# wizneteval.net
KiCad netlist of a schematic drawn in EAGLE
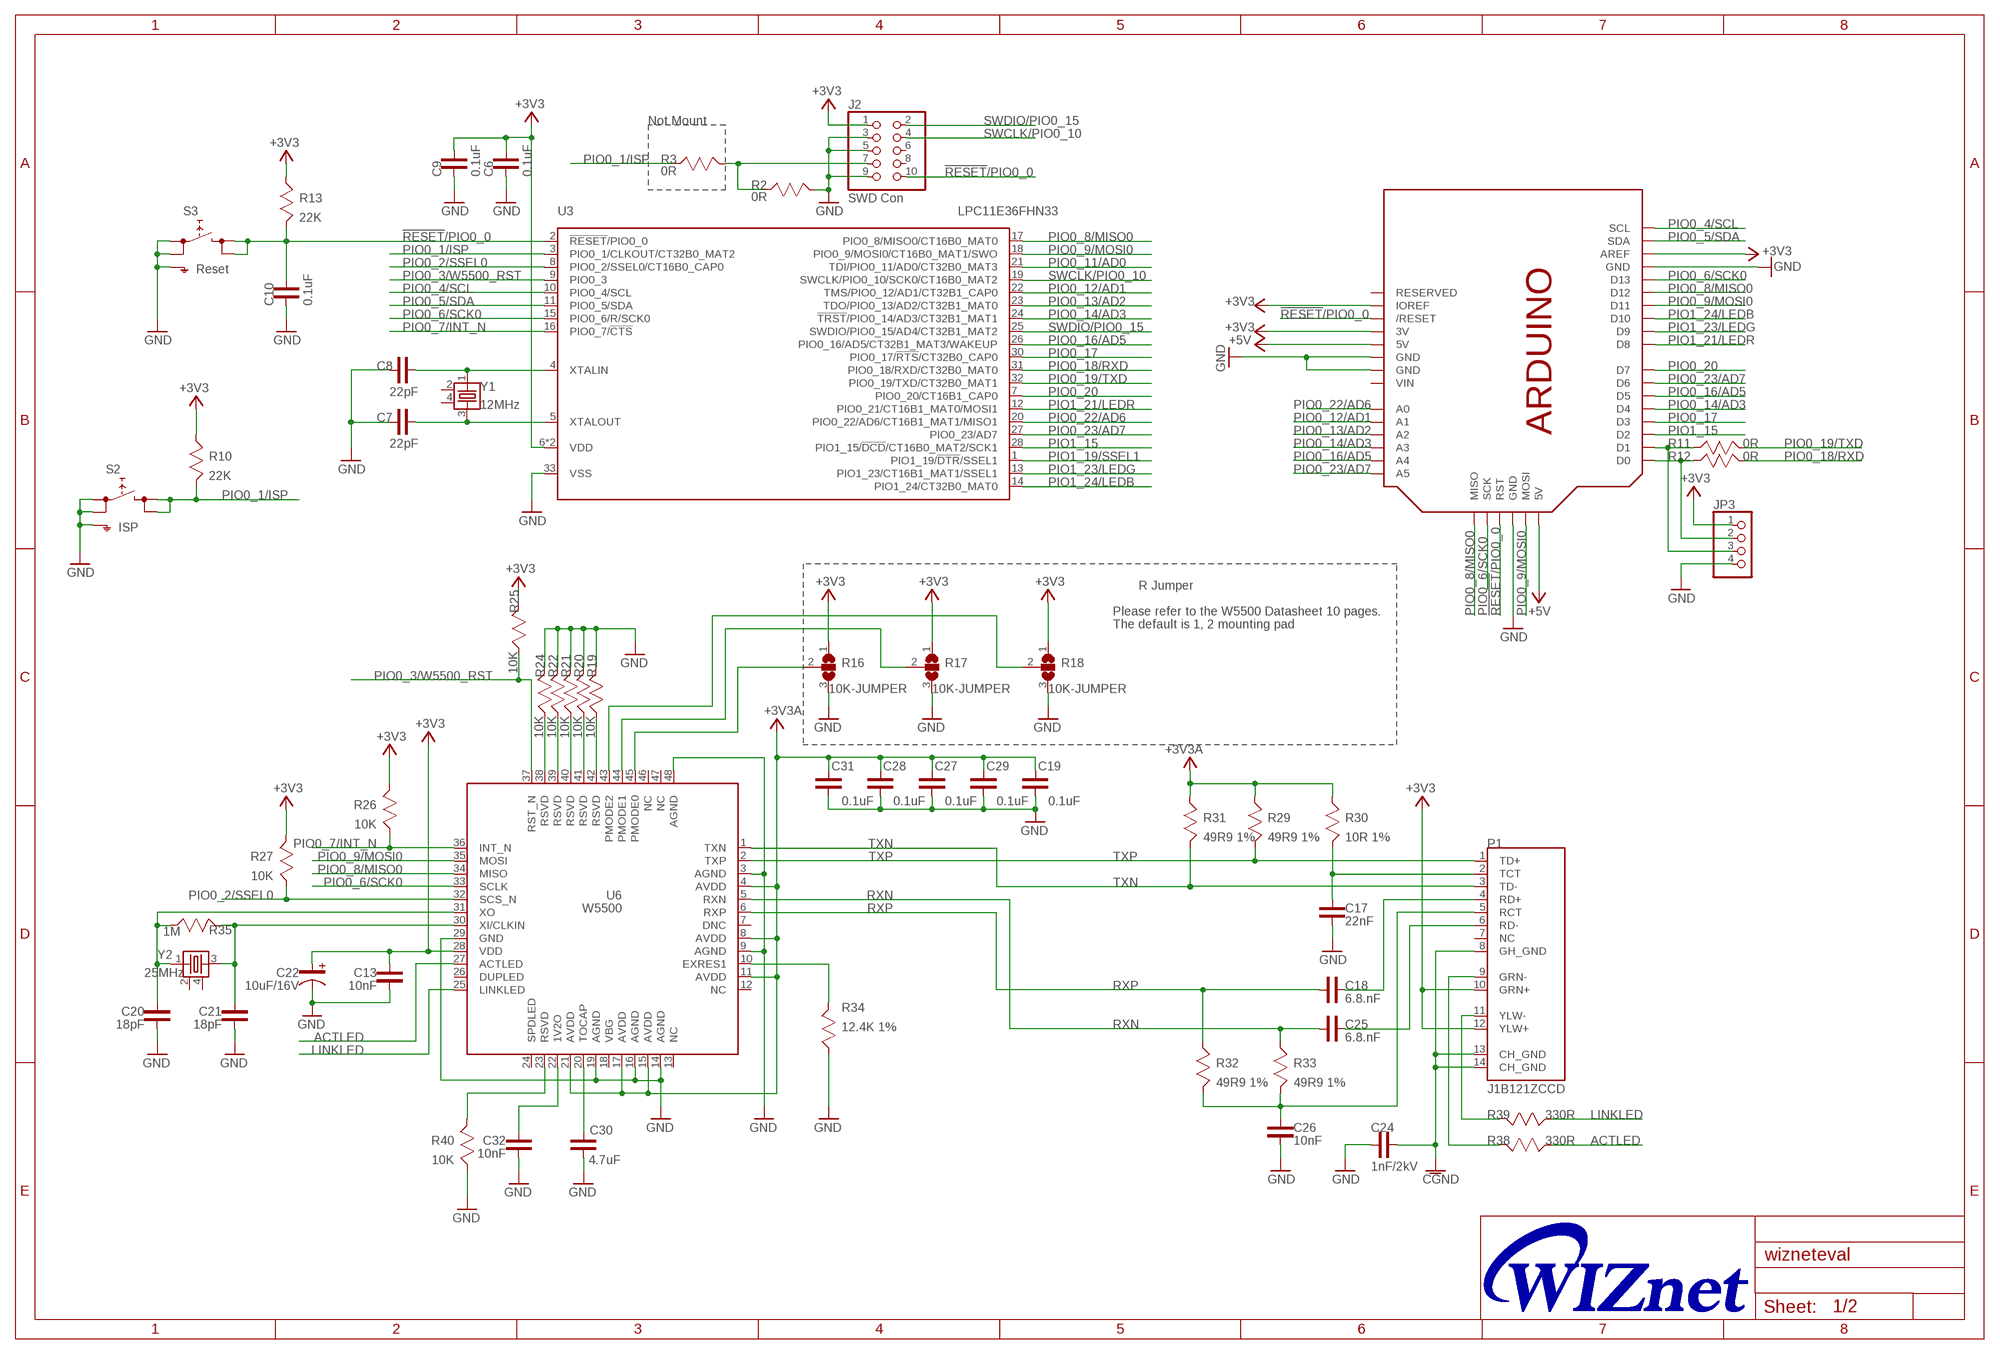
[diagram p0: schematic, sheet 1]
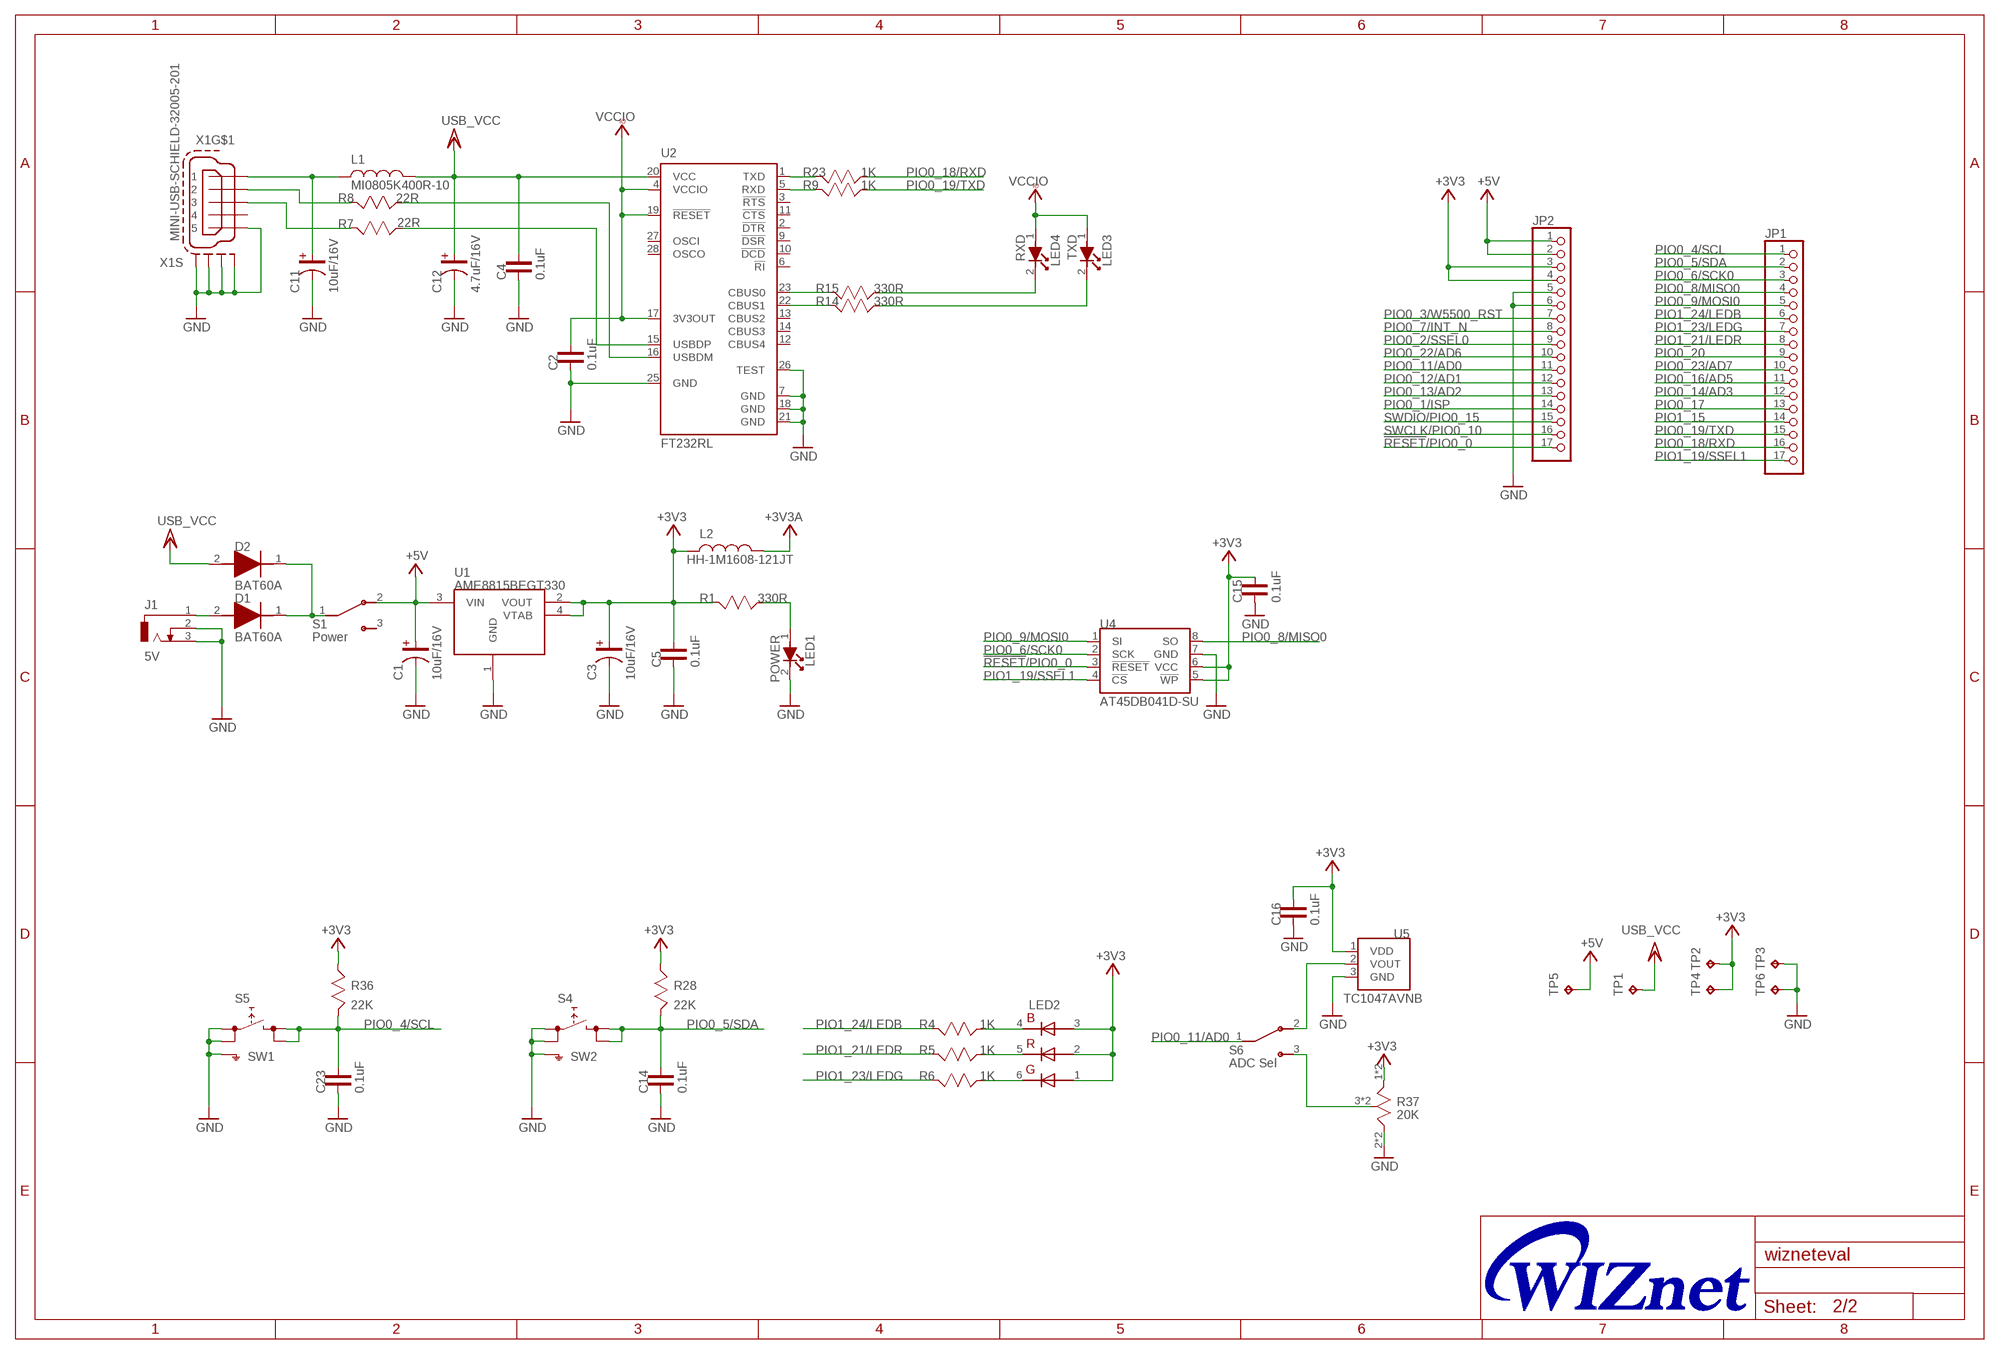
[diagram p1: schematic, sheet 2]

(export (version "E")
  (design (tool "Eeschema 10.0.6"))
  (components
    (comp (ref "$$U$3")
      (value "ARDUINO_R3_ICSP")
      (footprint "eagle-import:ARDUINOR3_ICSP")
      (libsource (lib "eagle-import") (part "ARDUINO_R3_ICSP"))
    )
    (comp (ref "C6")
      (value "0.1uF")
      (footprint "eagle-import:C-1608")
      (libsource (lib "eagle-import") (part "C-1608"))
    )
    (comp (ref "C7")
      (value "22pF")
      (footprint "eagle-import:C-1608")
      (libsource (lib "eagle-import") (part "C-1608"))
    )
    (comp (ref "C8")
      (value "22pF")
      (footprint "eagle-import:C-1608")
      (libsource (lib "eagle-import") (part "C-1608"))
    )
    (comp (ref "C9")
      (value "0.1uF")
      (footprint "eagle-import:C-1608")
      (libsource (lib "eagle-import") (part "C-1608"))
    )
    (comp (ref "C10")
      (value "0.1uF")
      (footprint "eagle-import:C-1608")
      (libsource (lib "eagle-import") (part "C-1608"))
    )
    (comp (ref "C13")
      (value "10nF")
      (footprint "eagle-import:C-1608")
      (libsource (lib "eagle-import") (part "C-1608"))
    )
    (comp (ref "C17")
      (value "22nF")
      (footprint "eagle-import:C-1608")
      (libsource (lib "eagle-import") (part "C-1608"))
    )
    (comp (ref "C18")
      (value "6.8.nF")
      (footprint "eagle-import:C-1608")
      (libsource (lib "eagle-import") (part "C-1608"))
    )
    (comp (ref "C19")
      (value "0.1uF")
      (footprint "eagle-import:C-1608")
      (libsource (lib "eagle-import") (part "C-1608"))
    )
    (comp (ref "C20")
      (value "18pF")
      (footprint "eagle-import:C-1608")
      (libsource (lib "eagle-import") (part "C-1608"))
    )
    (comp (ref "C21")
      (value "18pF")
      (footprint "eagle-import:C-1608")
      (libsource (lib "eagle-import") (part "C-1608"))
    )
    (comp (ref "C22")
      (value "10uF/16V")
      (footprint "eagle-import:C-3216(TANTAL)")
      (libsource (lib "eagle-import") (part "C-3216(TANTAL)"))
    )
    (comp (ref "C24")
      (value "1nF/2kV")
      (footprint "eagle-import:C-4520")
      (libsource (lib "eagle-import") (part "C-4520"))
    )
    (comp (ref "C25")
      (value "6.8.nF")
      (footprint "eagle-import:C-1608")
      (libsource (lib "eagle-import") (part "C-1608"))
    )
    (comp (ref "C26")
      (value "10nF")
      (footprint "eagle-import:C-1608")
      (libsource (lib "eagle-import") (part "C-1608"))
    )
    (comp (ref "C27")
      (value "0.1uF")
      (footprint "eagle-import:C-1608")
      (libsource (lib "eagle-import") (part "C-1608"))
    )
    (comp (ref "C28")
      (value "0.1uF")
      (footprint "eagle-import:C-1608")
      (libsource (lib "eagle-import") (part "C-1608"))
    )
    (comp (ref "C29")
      (value "0.1uF")
      (footprint "eagle-import:C-1608")
      (libsource (lib "eagle-import") (part "C-1608"))
    )
    (comp (ref "C30")
      (value "4.7uF")
      (footprint "eagle-import:C-2012")
      (libsource (lib "eagle-import") (part "C-2012"))
    )
    (comp (ref "C31")
      (value "0.1uF")
      (footprint "eagle-import:C-1608")
      (libsource (lib "eagle-import") (part "C-1608"))
    )
    (comp (ref "C32")
      (value "10nF")
      (footprint "eagle-import:C-1608")
      (libsource (lib "eagle-import") (part "C-1608"))
    )
    (comp (ref "J2")
      (value "SWD Con")
      (footprint "eagle-import:2X5_1.27")
      (libsource (lib "eagle-import") (part "2X5_1.27"))
    )
    (comp (ref "JP3")
      (value "PINHD-1X4")
      (footprint "eagle-import:1X04")
      (libsource (lib "eagle-import") (part "PINHD-1X4"))
    )
    (comp (ref "P1")
      (value "J1B121ZCCD")
      (footprint "eagle-import:J1B121ZCCD")
      (libsource (lib "eagle-import") (part "J1B121ZCCD"))
    )
    (comp (ref "R2")
      (value "0R")
      (footprint "eagle-import:R-1608")
      (libsource (lib "eagle-import") (part "R-1608"))
    )
    (comp (ref "R3")
      (value "0R")
      (footprint "eagle-import:R-1608")
      (libsource (lib "eagle-import") (part "R-1608"))
    )
    (comp (ref "R10")
      (value "22K")
      (footprint "eagle-import:R-1608")
      (libsource (lib "eagle-import") (part "R-1608"))
    )
    (comp (ref "R11")
      (value "0R")
      (footprint "eagle-import:R-1608")
      (libsource (lib "eagle-import") (part "R-1608"))
    )
    (comp (ref "R12")
      (value "0R")
      (footprint "eagle-import:R-1608")
      (libsource (lib "eagle-import") (part "R-1608"))
    )
    (comp (ref "R13")
      (value "22K")
      (footprint "eagle-import:R-1608")
      (libsource (lib "eagle-import") (part "R-1608"))
    )
    (comp (ref "R16")
      (value "10K-JUMPER")
      (footprint "eagle-import:R-1608-JUMPER")
      (libsource (lib "eagle-import") (part "R-1608-JUMPER"))
    )
    (comp (ref "R17")
      (value "10K-JUMPER")
      (footprint "eagle-import:R-1608-JUMPER")
      (libsource (lib "eagle-import") (part "R-1608-JUMPER"))
    )
    (comp (ref "R18")
      (value "10K-JUMPER")
      (footprint "eagle-import:R-1608-JUMPER")
      (libsource (lib "eagle-import") (part "R-1608-JUMPER"))
    )
    (comp (ref "R19")
      (value "10K")
      (footprint "eagle-import:R-1608")
      (libsource (lib "eagle-import") (part "R-1608"))
    )
    (comp (ref "R20")
      (value "10K")
      (footprint "eagle-import:R-1608")
      (libsource (lib "eagle-import") (part "R-1608"))
    )
    (comp (ref "R21")
      (value "10K")
      (footprint "eagle-import:R-1608")
      (libsource (lib "eagle-import") (part "R-1608"))
    )
    (comp (ref "R22")
      (value "10K")
      (footprint "eagle-import:R-1608")
      (libsource (lib "eagle-import") (part "R-1608"))
    )
    (comp (ref "R24")
      (value "10K")
      (footprint "eagle-import:R-1608")
      (libsource (lib "eagle-import") (part "R-1608"))
    )
    (comp (ref "R25")
      (value "10K")
      (footprint "eagle-import:R-1608")
      (libsource (lib "eagle-import") (part "R-1608"))
    )
    (comp (ref "R26")
      (value "10K")
      (footprint "eagle-import:R-1608")
      (libsource (lib "eagle-import") (part "R-1608"))
    )
    (comp (ref "R27")
      (value "10K")
      (footprint "eagle-import:R-1608")
      (libsource (lib "eagle-import") (part "R-1608"))
    )
    (comp (ref "R29")
      (value "49R9 1%")
      (footprint "eagle-import:R-1608")
      (libsource (lib "eagle-import") (part "R-1608"))
    )
    (comp (ref "R30")
      (value "10R 1%")
      (footprint "eagle-import:R-1608")
      (libsource (lib "eagle-import") (part "R-1608"))
    )
    (comp (ref "R31")
      (value "49R9 1%")
      (footprint "eagle-import:R-1608")
      (libsource (lib "eagle-import") (part "R-1608"))
    )
    (comp (ref "R32")
      (value "49R9 1%")
      (footprint "eagle-import:R-1608")
      (libsource (lib "eagle-import") (part "R-1608"))
    )
    (comp (ref "R33")
      (value "49R9 1%")
      (footprint "eagle-import:R-1608")
      (libsource (lib "eagle-import") (part "R-1608"))
    )
    (comp (ref "R34")
      (value "12.4K 1%")
      (footprint "eagle-import:R-1608")
      (libsource (lib "eagle-import") (part "R-1608"))
    )
    (comp (ref "R35")
      (value "1M")
      (footprint "eagle-import:R-1608")
      (libsource (lib "eagle-import") (part "R-1608"))
    )
    (comp (ref "R38")
      (value "330R")
      (footprint "eagle-import:R-1608")
      (libsource (lib "eagle-import") (part "R-1608"))
    )
    (comp (ref "R39")
      (value "330R")
      (footprint "eagle-import:R-1608")
      (libsource (lib "eagle-import") (part "R-1608"))
    )
    (comp (ref "R40")
      (value "10K")
      (footprint "eagle-import:R-1608")
      (libsource (lib "eagle-import") (part "R-1608"))
    )
    (comp (ref "S2")
      (value "ISP")
      (footprint "eagle-import:SKHMPXE010")
      (libsource (lib "eagle-import") (part "SKHMPE010S"))
    )
    (comp (ref "S3")
      (value "Reset")
      (footprint "eagle-import:SKHMPXE010")
      (libsource (lib "eagle-import") (part "SKHMPE010S"))
    )
    (comp (ref "U3")
      (value "LPC11E36FHN33")
      (footprint "eagle-import:SOT-HVQFN33")
      (libsource (lib "eagle-import") (part "LPC11E36FHN33"))
    )
    (comp (ref "U6")
      (value "W5500")
      (footprint "eagle-import:W5500")
      (libsource (lib "eagle-import") (part "W5500"))
    )
    (comp (ref "Y1")
      (value "12MHz")
      (footprint "eagle-import:XTAL3225")
      (libsource (lib "eagle-import") (part "XTAL3225"))
    )
    (comp (ref "Y2")
      (value "25MHz")
      (footprint "eagle-import:XTAL3225")
      (libsource (lib "eagle-import") (part "XTAL3225"))
    )
    (comp (ref "C1")
      (value "10uF/16V")
      (footprint "eagle-import:C-3216(TANTAL)")
      (libsource (lib "eagle-import") (part "C-3216(TANTAL)"))
    )
    (comp (ref "C2")
      (value "0.1uF")
      (footprint "eagle-import:C-1608")
      (libsource (lib "eagle-import") (part "C-1608"))
    )
    (comp (ref "C3")
      (value "10uF/16V")
      (footprint "eagle-import:C-3216(TANTAL)")
      (libsource (lib "eagle-import") (part "C-3216(TANTAL)"))
    )
    (comp (ref "C4")
      (value "0.1uF")
      (footprint "eagle-import:C-1608")
      (libsource (lib "eagle-import") (part "C-1608"))
    )
    (comp (ref "C5")
      (value "0.1uF")
      (footprint "eagle-import:C-1608")
      (libsource (lib "eagle-import") (part "C-1608"))
    )
    (comp (ref "C11")
      (value "10uF/16V")
      (footprint "eagle-import:C-3216(TANTAL)")
      (libsource (lib "eagle-import") (part "C-3216(TANTAL)"))
    )
    (comp (ref "C12")
      (value "4.7uF/16V")
      (footprint "eagle-import:C-3216(TANTAL)")
      (libsource (lib "eagle-import") (part "C-3216(TANTAL)"))
    )
    (comp (ref "C14")
      (value "0.1uF")
      (footprint "eagle-import:C-1608")
      (libsource (lib "eagle-import") (part "C-1608"))
    )
    (comp (ref "C15")
      (value "0.1uF")
      (footprint "eagle-import:C-1608")
      (libsource (lib "eagle-import") (part "C-1608"))
    )
    (comp (ref "C16")
      (value "0.1uF")
      (footprint "eagle-import:C-1608")
      (libsource (lib "eagle-import") (part "C-1608"))
    )
    (comp (ref "C23")
      (value "0.1uF")
      (footprint "eagle-import:C-1608")
      (libsource (lib "eagle-import") (part "C-1608"))
    )
    (comp (ref "D1")
      (value "BAT60A")
      (footprint "eagle-import:BAT60A")
      (libsource (lib "eagle-import") (part "BAT60A"))
    )
    (comp (ref "D2")
      (value "BAT60A")
      (footprint "eagle-import:BAT60A")
      (libsource (lib "eagle-import") (part "BAT60A"))
    )
    (comp (ref "J1")
      (value "5V")
      (footprint "eagle-import:DCJ0202")
      (libsource (lib "eagle-import") (part "DCJ0202"))
    )
    (comp (ref "JP1")
      (value "PINHD-1X17")
      (footprint "eagle-import:1X17")
      (libsource (lib "eagle-import") (part "PINHD-1X17"))
    )
    (comp (ref "JP2")
      (value "PINHD-1X17")
      (footprint "eagle-import:1X17")
      (libsource (lib "eagle-import") (part "PINHD-1X17"))
    )
    (comp (ref "L1")
      (value "MI0805K400R-10")
      (footprint "eagle-import:L-2012")
      (libsource (lib "eagle-import") (part "L-2012"))
    )
    (comp (ref "L2")
      (value "HH-1M1608-121JT")
      (footprint "eagle-import:L-1608")
      (libsource (lib "eagle-import") (part "L-1608"))
    )
    (comp (ref "LED1")
      (value "POWER")
      (footprint "eagle-import:LED-1608")
      (libsource (lib "eagle-import") (part "LED-1608"))
    )
    (comp (ref "LED2")
      (value "LS5050RGB5050")
      (footprint "eagle-import:LS5050RGB")
      (libsource (lib "eagle-import") (part "LS5050RGB5050"))
    )
    (comp (ref "LED3")
      (value "TXD")
      (footprint "eagle-import:LED-1608")
      (libsource (lib "eagle-import") (part "LED-1608"))
    )
    (comp (ref "LED4")
      (value "RXD")
      (footprint "eagle-import:LED-1608")
      (libsource (lib "eagle-import") (part "LED-1608"))
    )
    (comp (ref "R1")
      (value "330R")
      (footprint "eagle-import:R-1608")
      (libsource (lib "eagle-import") (part "R-1608"))
    )
    (comp (ref "R4")
      (value "1K")
      (footprint "eagle-import:R-1608")
      (libsource (lib "eagle-import") (part "R-1608"))
    )
    (comp (ref "R5")
      (value "1K")
      (footprint "eagle-import:R-1608")
      (libsource (lib "eagle-import") (part "R-1608"))
    )
    (comp (ref "R6")
      (value "1K")
      (footprint "eagle-import:R-1608")
      (libsource (lib "eagle-import") (part "R-1608"))
    )
    (comp (ref "R7")
      (value "22R")
      (footprint "eagle-import:R-1608")
      (libsource (lib "eagle-import") (part "R-1608"))
    )
    (comp (ref "R8")
      (value "22R")
      (footprint "eagle-import:R-1608")
      (libsource (lib "eagle-import") (part "R-1608"))
    )
    (comp (ref "R9")
      (value "1K")
      (footprint "eagle-import:R-1608")
      (libsource (lib "eagle-import") (part "R-1608"))
    )
    (comp (ref "R14")
      (value "330R")
      (footprint "eagle-import:R-1608")
      (libsource (lib "eagle-import") (part "R-1608"))
    )
    (comp (ref "R15")
      (value "330R")
      (footprint "eagle-import:R-1608")
      (libsource (lib "eagle-import") (part "R-1608"))
    )
    (comp (ref "R23")
      (value "1K")
      (footprint "eagle-import:R-1608")
      (libsource (lib "eagle-import") (part "R-1608"))
    )
    (comp (ref "R28")
      (value "22K")
      (footprint "eagle-import:R-1608")
      (libsource (lib "eagle-import") (part "R-1608"))
    )
    (comp (ref "R36")
      (value "22K")
      (footprint "eagle-import:R-1608")
      (libsource (lib "eagle-import") (part "R-1608"))
    )
    (comp (ref "R37")
      (value "20K")
      (footprint "eagle-import:RES-VAR-PT10(DUAL)")
      (libsource (lib "eagle-import") (part "RES-VAR-PT10DAUL"))
    )
    (comp (ref "S1")
      (value "Power")
      (footprint "eagle-import:IMMS-12H")
      (libsource (lib "eagle-import") (part "IMMS-12H"))
    )
    (comp (ref "S4")
      (value "SW2")
      (footprint "eagle-import:SKHMPXE010")
      (libsource (lib "eagle-import") (part "SKHMPE010S"))
    )
    (comp (ref "S5")
      (value "SW1")
      (footprint "eagle-import:SKHMPXE010")
      (libsource (lib "eagle-import") (part "SKHMPE010S"))
    )
    (comp (ref "S6")
      (value "ADC Sel")
      (footprint "eagle-import:IMMS-12H")
      (libsource (lib "eagle-import") (part "IMMS-12H"))
    )
    (comp (ref "TP1")
      (value "TPB1,27")
      (footprint "eagle-import:B1,27")
      (libsource (lib "eagle-import") (part "TPB1,27"))
    )
    (comp (ref "TP2")
      (value "TPB1,27")
      (footprint "eagle-import:B1,27")
      (libsource (lib "eagle-import") (part "TPB1,27"))
    )
    (comp (ref "TP3")
      (value "TPB1,27")
      (footprint "eagle-import:B1,27")
      (libsource (lib "eagle-import") (part "TPB1,27"))
    )
    (comp (ref "TP4")
      (value "TPB1,27")
      (footprint "eagle-import:B1,27")
      (libsource (lib "eagle-import") (part "TPB1,27"))
    )
    (comp (ref "TP5")
      (value "TPB1,27")
      (footprint "eagle-import:B1,27")
      (libsource (lib "eagle-import") (part "TPB1,27"))
    )
    (comp (ref "TP6")
      (value "TPB1,27")
      (footprint "eagle-import:B1,27")
      (libsource (lib "eagle-import") (part "TPB1,27"))
    )
    (comp (ref "U1")
      (value "AME8815BEGT330")
      (footprint "eagle-import:SOT-223")
      (libsource (lib "eagle-import") (part "AME8815BEGT330"))
    )
    (comp (ref "U2")
      (value "FT232RL")
      (footprint "eagle-import:SSOP28")
      (libsource (lib "eagle-import") (part "FT232RL"))
    )
    (comp (ref "U4")
      (value "AT45DB041D-SU")
      (footprint "eagle-import:8S2")
      (libsource (lib "eagle-import") (part "AT45DB041D-SU"))
    )
    (comp (ref "U5")
      (value "TC1047AVNB")
      (footprint "eagle-import:SOT23")
      (libsource (lib "eagle-import") (part "TC1047AVNB"))
    )
    (comp (ref "X1")
      (value "MINI-USB-SCHIELD-32005-201")
      (footprint "eagle-import:32005-201")
      (libsource (lib "eagle-import") (part "MINI-USB-SCHIELD-32005-201"))
    )
  )
  (nets
    (net (code "1") (name "+3V3") (class "Default")
      (node (ref "$$U$3") (pin "3V") (pinfunction "3V_3V") (pintype "power_in"))
      (node (ref "$$U$3") (pin "AREF") (pinfunction "AREF_AREF") (pintype "bidirectional"))
      (node (ref "$$U$3") (pin "IOREF") (pinfunction "IOREF_IOREF") (pintype "output"))
      (node (ref "C13") (pin "2") (pinfunction "P$2_2") (pintype "passive"))
      (node (ref "C15") (pin "2") (pinfunction "P$2_2") (pintype "passive"))
      (node (ref "C16") (pin "2") (pinfunction "P$2_2") (pintype "passive"))
      (node (ref "C22") (pin "1") (pinfunction "1_1") (pintype "passive"))
      (node (ref "C3") (pin "1") (pinfunction "1_1") (pintype "passive"))
      (node (ref "C5") (pin "2") (pinfunction "P$2_2") (pintype "passive"))
      (node (ref "C6") (pin "2") (pinfunction "P$2_2") (pintype "passive"))
      (node (ref "C9") (pin "2") (pinfunction "P$2_2") (pintype "passive"))
      (node (ref "J2") (pin "1") (pinfunction "1_1") (pintype "passive"))
      (node (ref "JP2") (pin "3") (pinfunction "3_3") (pintype "passive"))
      (node (ref "JP2") (pin "4") (pinfunction "4_4") (pintype "passive"))
      (node (ref "JP3") (pin "1") (pinfunction "1_1") (pintype "passive"))
      (node (ref "L2") (pin "1") (pinfunction "1_1") (pintype "passive"))
      (node (ref "LED2") (pin "1") (pinfunction "GREEN_A_1") (pintype "bidirectional"))
      (node (ref "LED2") (pin "2") (pinfunction "RED_A_2") (pintype "bidirectional"))
      (node (ref "LED2") (pin "3") (pinfunction "BLUE_A_3") (pintype "bidirectional"))
      (node (ref "P1") (pin "10") (pinfunction "GRN+_10") (pintype "passive"))
      (node (ref "P1") (pin "12") (pinfunction "YLW+_12") (pintype "passive"))
      (node (ref "R1") (pin "1") (pinfunction "P$1_1") (pintype "passive"))
      (node (ref "R10") (pin "2") (pinfunction "P$2_2") (pintype "passive"))
      (node (ref "R13") (pin "2") (pinfunction "P$2_2") (pintype "passive"))
      (node (ref "R16") (pin "1") (pinfunction "1_1") (pintype "passive"))
      (node (ref "R17") (pin "1") (pinfunction "1_1") (pintype "passive"))
      (node (ref "R18") (pin "1") (pinfunction "1_1") (pintype "passive"))
      (node (ref "R25") (pin "2") (pinfunction "P$2_2") (pintype "passive"))
      (node (ref "R26") (pin "2") (pinfunction "P$2_2") (pintype "passive"))
      (node (ref "R27") (pin "2") (pinfunction "P$2_2") (pintype "passive"))
      (node (ref "R28") (pin "2") (pinfunction "P$2_2") (pintype "passive"))
      (node (ref "R36") (pin "2") (pinfunction "P$2_2") (pintype "passive"))
      (node (ref "R37") (pin "1") (pinfunction "P$1_1") (pintype "passive"))
      (node (ref "R37") (pin "P$1") (pinfunction "P$1_P$1") (pintype "passive"))
      (node (ref "TP2") (pin "TP") (pinfunction "TP_TP") (pintype "input"))
      (node (ref "TP4") (pin "TP") (pinfunction "TP_TP") (pintype "input"))
      (node (ref "U1") (pin "2") (pinfunction "VOUT_2") (pintype "passive"))
      (node (ref "U1") (pin "4") (pinfunction "VTAB_4") (pintype "passive"))
      (node (ref "U3") (pin "29") (pinfunction "VDD_29") (pintype "power_in"))
      (node (ref "U3") (pin "6") (pinfunction "VDD_6") (pintype "power_in"))
      (node (ref "U4") (pin "5") (pinfunction "~{WP}_5") (pintype "passive"))
      (node (ref "U4") (pin "6") (pinfunction "VCC_6") (pintype "passive"))
      (node (ref "U5") (pin "1") (pinfunction "VDD_1") (pintype "passive"))
      (node (ref "U6") (pin "28") (pinfunction "VDD_28") (pintype "passive"))
    )
    (net (code "2") (name "+3V3A") (class "Default")
      (node (ref "C19") (pin "2") (pinfunction "P$2_2") (pintype "passive"))
      (node (ref "C27") (pin "2") (pinfunction "P$2_2") (pintype "passive"))
      (node (ref "C28") (pin "2") (pinfunction "P$2_2") (pintype "passive"))
      (node (ref "C29") (pin "2") (pinfunction "P$2_2") (pintype "passive"))
      (node (ref "C31") (pin "2") (pinfunction "P$2_2") (pintype "passive"))
      (node (ref "L2") (pin "P$2") (pinfunction "2_P$2") (pintype "passive"))
      (node (ref "R29") (pin "2") (pinfunction "P$2_2") (pintype "passive"))
      (node (ref "R30") (pin "2") (pinfunction "P$2_2") (pintype "passive"))
      (node (ref "R31") (pin "2") (pinfunction "P$2_2") (pintype "passive"))
      (node (ref "U6") (pin "11") (pinfunction "AVDD_11") (pintype "passive"))
      (node (ref "U6") (pin "15") (pinfunction "AVDD_15") (pintype "passive"))
      (node (ref "U6") (pin "17") (pinfunction "AVDD_17") (pintype "passive"))
      (node (ref "U6") (pin "21") (pinfunction "AVDD_21") (pintype "passive"))
      (node (ref "U6") (pin "4") (pinfunction "AVDD_4") (pintype "passive"))
      (node (ref "U6") (pin "8") (pinfunction "AVDD_8") (pintype "passive"))
    )
    (net (code "3") (name "+5V") (class "Default")
      (node (ref "$$U$3") (pin "5V") (pinfunction "5V_5V") (pintype "power_in"))
      (node (ref "$$U$3") (pin "5V_ICSP") (pinfunction "5V_5V_ICSP") (pintype "passive"))
      (node (ref "C1") (pin "1") (pinfunction "1_1") (pintype "passive"))
      (node (ref "JP2") (pin "1") (pinfunction "1_1") (pintype "passive"))
      (node (ref "JP2") (pin "2") (pinfunction "2_2") (pintype "passive"))
      (node (ref "S1") (pin "2") (pinfunction "2_2") (pintype "passive"))
      (node (ref "TP5") (pin "TP") (pinfunction "TP_TP") (pintype "input"))
      (node (ref "U1") (pin "3") (pinfunction "VIN_3") (pintype "passive"))
    )
    (net (code "4") (name "ACTLED") (class "Default")
      (node (ref "R38") (pin "2") (pinfunction "P$2_2") (pintype "passive"))
      (node (ref "U6") (pin "27") (pinfunction "ACTLED_27") (pintype "passive"))
    )
    (net (code "5") (name "CGND") (class "Default")
      (node (ref "C24") (pin "2") (pinfunction "P$2_2") (pintype "passive"))
      (node (ref "P1") (pin "13") (pinfunction "CH_GND_13") (pintype "passive"))
      (node (ref "P1") (pin "14") (pinfunction "CH_GND_14") (pintype "passive"))
      (node (ref "P1") (pin "8") (pinfunction "GH_GND_8") (pintype "passive"))
    )
    (net (code "6") (name "GND") (class "Default")
      (node (ref "$$U$3") (pin "GND") (pinfunction "GND_GND") (pintype "power_in"))
      (node (ref "$$U$3") (pin "GND@1") (pinfunction "GND_GND@1") (pintype "power_in"))
      (node (ref "$$U$3") (pin "GND@2") (pinfunction "GND_GND@2") (pintype "passive"))
      (node (ref "$$U$3") (pin "GND@3") (pinfunction "GND_GND@3") (pintype "power_in"))
      (node (ref "C1") (pin "2") (pinfunction "2_2") (pintype "passive"))
      (node (ref "C10") (pin "1") (pinfunction "P$1_1") (pintype "passive"))
      (node (ref "C11") (pin "2") (pinfunction "2_2") (pintype "passive"))
      (node (ref "C12") (pin "2") (pinfunction "2_2") (pintype "passive"))
      (node (ref "C13") (pin "1") (pinfunction "P$1_1") (pintype "passive"))
      (node (ref "C14") (pin "1") (pinfunction "P$1_1") (pintype "passive"))
      (node (ref "C15") (pin "1") (pinfunction "P$1_1") (pintype "passive"))
      (node (ref "C16") (pin "1") (pinfunction "P$1_1") (pintype "passive"))
      (node (ref "C17") (pin "1") (pinfunction "P$1_1") (pintype "passive"))
      (node (ref "C19") (pin "1") (pinfunction "P$1_1") (pintype "passive"))
      (node (ref "C2") (pin "1") (pinfunction "P$1_1") (pintype "passive"))
      (node (ref "C20") (pin "1") (pinfunction "P$1_1") (pintype "passive"))
      (node (ref "C21") (pin "1") (pinfunction "P$1_1") (pintype "passive"))
      (node (ref "C22") (pin "2") (pinfunction "2_2") (pintype "passive"))
      (node (ref "C23") (pin "1") (pinfunction "P$1_1") (pintype "passive"))
      (node (ref "C24") (pin "1") (pinfunction "P$1_1") (pintype "passive"))
      (node (ref "C26") (pin "1") (pinfunction "P$1_1") (pintype "passive"))
      (node (ref "C27") (pin "1") (pinfunction "P$1_1") (pintype "passive"))
      (node (ref "C28") (pin "1") (pinfunction "P$1_1") (pintype "passive"))
      (node (ref "C29") (pin "1") (pinfunction "P$1_1") (pintype "passive"))
      (node (ref "C3") (pin "2") (pinfunction "2_2") (pintype "passive"))
      (node (ref "C30") (pin "P$1") (pinfunction "P$1_P$1") (pintype "passive"))
      (node (ref "C31") (pin "1") (pinfunction "P$1_1") (pintype "passive"))
      (node (ref "C32") (pin "1") (pinfunction "P$1_1") (pintype "passive"))
      (node (ref "C4") (pin "1") (pinfunction "P$1_1") (pintype "passive"))
      (node (ref "C5") (pin "1") (pinfunction "P$1_1") (pintype "passive"))
      (node (ref "C6") (pin "1") (pinfunction "P$1_1") (pintype "passive"))
      (node (ref "C7") (pin "1") (pinfunction "P$1_1") (pintype "passive"))
      (node (ref "C8") (pin "1") (pinfunction "P$1_1") (pintype "passive"))
      (node (ref "C9") (pin "1") (pinfunction "P$1_1") (pintype "passive"))
      (node (ref "J1") (pin "2") (pinfunction "2_2") (pintype "passive"))
      (node (ref "J1") (pin "3") (pinfunction "3_3") (pintype "passive"))
      (node (ref "J2") (pin "3") (pinfunction "3_3") (pintype "passive"))
      (node (ref "J2") (pin "5") (pinfunction "5_5") (pintype "passive"))
      (node (ref "J2") (pin "9") (pinfunction "9_9") (pintype "passive"))
      (node (ref "JP2") (pin "5") (pinfunction "5_5") (pintype "passive"))
      (node (ref "JP2") (pin "6") (pinfunction "6_6") (pintype "passive"))
      (node (ref "JP3") (pin "4") (pinfunction "4_4") (pintype "passive"))
      (node (ref "LED1") (pin "2") (pinfunction "P$2_2") (pintype "bidirectional"))
      (node (ref "R16") (pin "3") (pinfunction "3_3") (pintype "passive"))
      (node (ref "R17") (pin "3") (pinfunction "3_3") (pintype "passive"))
      (node (ref "R18") (pin "3") (pinfunction "3_3") (pintype "passive"))
      (node (ref "R19") (pin "2") (pinfunction "P$2_2") (pintype "passive"))
      (node (ref "R2") (pin "1") (pinfunction "P$1_1") (pintype "passive"))
      (node (ref "R20") (pin "2") (pinfunction "P$2_2") (pintype "passive"))
      (node (ref "R21") (pin "2") (pinfunction "P$2_2") (pintype "passive"))
      (node (ref "R22") (pin "2") (pinfunction "P$2_2") (pintype "passive"))
      (node (ref "R24") (pin "2") (pinfunction "P$2_2") (pintype "passive"))
      (node (ref "R34") (pin "1") (pinfunction "P$1_1") (pintype "passive"))
      (node (ref "R37") (pin "2") (pinfunction "P$2_2") (pintype "passive"))
      (node (ref "R37") (pin "P$3") (pinfunction "P$2_P$3") (pintype "passive"))
      (node (ref "R40") (pin "1") (pinfunction "P$1_1") (pintype "passive"))
      (node (ref "S2") (pin "1") (pinfunction "1.1_1") (pintype "passive"))
      (node (ref "S2") (pin "2") (pinfunction "1.2_2") (pintype "passive"))
      (node (ref "S2") (pin "5") (pinfunction "SH_5") (pintype "passive"))
      (node (ref "S3") (pin "1") (pinfunction "1.1_1") (pintype "passive"))
      (node (ref "S3") (pin "2") (pinfunction "1.2_2") (pintype "passive"))
      (node (ref "S3") (pin "5") (pinfunction "SH_5") (pintype "passive"))
      (node (ref "S4") (pin "1") (pinfunction "1.1_1") (pintype "passive"))
      (node (ref "S4") (pin "2") (pinfunction "1.2_2") (pintype "passive"))
      (node (ref "S4") (pin "5") (pinfunction "SH_5") (pintype "passive"))
      (node (ref "S5") (pin "1") (pinfunction "1.1_1") (pintype "passive"))
      (node (ref "S5") (pin "2") (pinfunction "1.2_2") (pintype "passive"))
      (node (ref "S5") (pin "5") (pinfunction "SH_5") (pintype "passive"))
      (node (ref "TP3") (pin "TP") (pinfunction "TP_TP") (pintype "input"))
      (node (ref "TP6") (pin "TP") (pinfunction "TP_TP") (pintype "input"))
      (node (ref "U1") (pin "1") (pinfunction "GND_1") (pintype "passive"))
      (node (ref "U2") (pin "18") (pinfunction "GND_18") (pintype "power_in"))
      (node (ref "U2") (pin "21") (pinfunction "GND_21") (pintype "power_in"))
      (node (ref "U2") (pin "25") (pinfunction "GND_25") (pintype "power_in"))
      (node (ref "U2") (pin "26") (pinfunction "TEST_26") (pintype "input"))
      (node (ref "U2") (pin "7") (pinfunction "GND_7") (pintype "power_in"))
      (node (ref "U3") (pin "33") (pinfunction "VSS_33") (pintype "power_in"))
      (node (ref "U4") (pin "7") (pinfunction "GND_7") (pintype "passive"))
      (node (ref "U5") (pin "3") (pinfunction "GND_3") (pintype "passive"))
      (node (ref "U6") (pin "14") (pinfunction "AGND_14") (pintype "passive"))
      (node (ref "U6") (pin "16") (pinfunction "AGND_16") (pintype "passive"))
      (node (ref "U6") (pin "19") (pinfunction "AGND_19") (pintype "passive"))
      (node (ref "U6") (pin "29") (pinfunction "GND_29") (pintype "passive"))
      (node (ref "U6") (pin "3") (pinfunction "AGND_3") (pintype "passive"))
      (node (ref "U6") (pin "48") (pinfunction "AGND_48") (pintype "passive"))
      (node (ref "U6") (pin "9") (pinfunction "AGND_9") (pintype "passive"))
      (node (ref "X1") (pin "5") (pinfunction "5_5") (pintype "passive"))
      (node (ref "X1") (pin "M1") (pinfunction "S1_M1") (pintype "passive"))
      (node (ref "X1") (pin "M2") (pinfunction "S2_M2") (pintype "passive"))
      (node (ref "X1") (pin "M3") (pinfunction "S3_M3") (pintype "passive"))
      (node (ref "X1") (pin "M4") (pinfunction "S4_M4") (pintype "passive"))
    )
    (net (code "7") (name "LINKLED") (class "Default")
      (node (ref "R39") (pin "2") (pinfunction "P$2_2") (pintype "passive"))
      (node (ref "U6") (pin "25") (pinfunction "LINKLED_25") (pintype "passive"))
    )
    (net (code "8") (name "Net-(C7-P$2)") (class "Default")
      (node (ref "C7") (pin "2") (pinfunction "P$2_2") (pintype "passive"))
      (node (ref "U3") (pin "5") (pinfunction "XTALOUT_5") (pintype "output"))
      (node (ref "Y1") (pin "3") (pinfunction "3_3") (pintype "passive"))
    )
    (net (code "9") (name "Net-(C8-P$2)") (class "Default")
      (node (ref "C8") (pin "2") (pinfunction "P$2_2") (pintype "passive"))
      (node (ref "U3") (pin "4") (pinfunction "XTALIN_4") (pintype "input"))
      (node (ref "Y1") (pin "1") (pinfunction "1_1") (pintype "passive"))
    )
    (net (code "10") (name "Net-(C11-Pad1)") (class "Default")
      (node (ref "C11") (pin "1") (pinfunction "1_1") (pintype "passive"))
      (node (ref "L1") (pin "1") (pinfunction "1_1") (pintype "passive"))
      (node (ref "X1") (pin "1") (pinfunction "1_1") (pintype "passive"))
    )
    (net (code "11") (name "Net-(C17-P$2)") (class "Default")
      (node (ref "C17") (pin "2") (pinfunction "P$2_2") (pintype "passive"))
      (node (ref "P1") (pin "2") (pinfunction "TCT_2") (pintype "passive"))
      (node (ref "R30") (pin "1") (pinfunction "P$1_1") (pintype "passive"))
    )
    (net (code "12") (name "Net-(C18-P$1)") (class "Default")
      (node (ref "C18") (pin "1") (pinfunction "P$1_1") (pintype "passive"))
      (node (ref "P1") (pin "4") (pinfunction "RD+_4") (pintype "passive"))
    )
    (net (code "13") (name "Net-(C20-P$2)") (class "Default")
      (node (ref "C20") (pin "2") (pinfunction "P$2_2") (pintype "passive"))
      (node (ref "R35") (pin "1") (pinfunction "P$1_1") (pintype "passive"))
      (node (ref "U6") (pin "31") (pinfunction "XO_31") (pintype "passive"))
      (node (ref "Y2") (pin "1") (pinfunction "1_1") (pintype "passive"))
    )
    (net (code "14") (name "Net-(C21-P$2)") (class "Default")
      (node (ref "C21") (pin "2") (pinfunction "P$2_2") (pintype "passive"))
      (node (ref "R35") (pin "2") (pinfunction "P$2_2") (pintype "passive"))
      (node (ref "U6") (pin "30") (pinfunction "XI/CLKIN_30") (pintype "passive"))
      (node (ref "Y2") (pin "3") (pinfunction "3_3") (pintype "passive"))
    )
    (net (code "15") (name "Net-(C25-P$1)") (class "Default")
      (node (ref "C25") (pin "1") (pinfunction "P$1_1") (pintype "passive"))
      (node (ref "P1") (pin "6") (pinfunction "RD-_6") (pintype "passive"))
    )
    (net (code "16") (name "Net-(C26-P$2)") (class "Default")
      (node (ref "C26") (pin "2") (pinfunction "P$2_2") (pintype "passive"))
      (node (ref "P1") (pin "5") (pinfunction "RCT_5") (pintype "passive"))
      (node (ref "R32") (pin "1") (pinfunction "P$1_1") (pintype "passive"))
      (node (ref "R33") (pin "1") (pinfunction "P$1_1") (pintype "passive"))
    )
    (net (code "17") (name "Net-(C32-P$2)") (class "Default")
      (node (ref "C32") (pin "2") (pinfunction "P$2_2") (pintype "passive"))
      (node (ref "U6") (pin "22") (pinfunction "1V2O_22") (pintype "passive"))
    )
    (net (code "18") (name "Net-(D1-Pad1)") (class "Default")
      (node (ref "D1") (pin "1") (pinfunction "1_1") (pintype "bidirectional"))
      (node (ref "D2") (pin "1") (pinfunction "1_1") (pintype "bidirectional"))
      (node (ref "S1") (pin "1") (pinfunction "1_1") (pintype "passive"))
    )
    (net (code "19") (name "Net-(D1-Pad2)") (class "Default")
      (node (ref "D1") (pin "2") (pinfunction "2_2") (pintype "bidirectional"))
      (node (ref "J1") (pin "1") (pinfunction "1_1") (pintype "passive"))
    )
    (net (code "20") (name "Net-(LED1-P$1)") (class "Default")
      (node (ref "LED1") (pin "1") (pinfunction "P$1_1") (pintype "bidirectional"))
      (node (ref "R1") (pin "2") (pinfunction "P$2_2") (pintype "passive"))
    )
    (net (code "21") (name "Net-(LED2-BLUE_C)") (class "Default")
      (node (ref "LED2") (pin "4") (pinfunction "BLUE_C_4") (pintype "bidirectional"))
      (node (ref "R4") (pin "2") (pinfunction "P$2_2") (pintype "passive"))
    )
    (net (code "22") (name "Net-(LED2-GREEN_C)") (class "Default")
      (node (ref "LED2") (pin "6") (pinfunction "GREEN_C_6") (pintype "bidirectional"))
      (node (ref "R6") (pin "2") (pinfunction "P$2_2") (pintype "passive"))
    )
    (net (code "23") (name "Net-(LED2-RED_C)") (class "Default")
      (node (ref "LED2") (pin "5") (pinfunction "RED_C_5") (pintype "bidirectional"))
      (node (ref "R5") (pin "2") (pinfunction "P$2_2") (pintype "passive"))
    )
    (net (code "24") (name "Net-(LED3-P$2)") (class "Default")
      (node (ref "LED3") (pin "2") (pinfunction "P$2_2") (pintype "bidirectional"))
      (node (ref "R14") (pin "2") (pinfunction "P$2_2") (pintype "passive"))
    )
    (net (code "25") (name "Net-(LED4-P$2)") (class "Default")
      (node (ref "LED4") (pin "2") (pinfunction "P$2_2") (pintype "bidirectional"))
      (node (ref "R15") (pin "2") (pinfunction "P$2_2") (pintype "passive"))
    )
    (net (code "26") (name "Net-(P1-GRN-)") (class "Default")
      (node (ref "P1") (pin "9") (pinfunction "GRN-_9") (pintype "passive"))
      (node (ref "R38") (pin "1") (pinfunction "P$1_1") (pintype "passive"))
    )
    (net (code "27") (name "Net-(P1-YLW-)") (class "Default")
      (node (ref "P1") (pin "11") (pinfunction "YLW-_11") (pintype "passive"))
      (node (ref "R39") (pin "1") (pinfunction "P$1_1") (pintype "passive"))
    )
    (net (code "28") (name "Net-(R2-P$2)") (class "Default")
      (node (ref "J2") (pin "7") (pinfunction "7_7") (pintype "passive"))
      (node (ref "R2") (pin "2") (pinfunction "P$2_2") (pintype "passive"))
      (node (ref "R3") (pin "1") (pinfunction "P$1_1") (pintype "passive"))
    )
    (net (code "29") (name "Net-(R7-P$1)") (class "Default")
      (node (ref "R7") (pin "1") (pinfunction "P$1_1") (pintype "passive"))
      (node (ref "X1") (pin "3") (pinfunction "3_3") (pintype "passive"))
    )
    (net (code "30") (name "Net-(R7-P$2)") (class "Default")
      (node (ref "R7") (pin "2") (pinfunction "P$2_2") (pintype "passive"))
      (node (ref "U2") (pin "15") (pinfunction "USBDP_15") (pintype "bidirectional"))
    )
    (net (code "31") (name "Net-(R8-P$1)") (class "Default")
      (node (ref "R8") (pin "1") (pinfunction "P$1_1") (pintype "passive"))
      (node (ref "X1") (pin "2") (pinfunction "2_2") (pintype "passive"))
    )
    (net (code "32") (name "Net-(R8-P$2)") (class "Default")
      (node (ref "R8") (pin "2") (pinfunction "P$2_2") (pintype "passive"))
      (node (ref "U2") (pin "16") (pinfunction "USBDM_16") (pintype "bidirectional"))
    )
    (net (code "33") (name "Net-(R9-P$1)") (class "Default")
      (node (ref "R9") (pin "1") (pinfunction "P$1_1") (pintype "passive"))
      (node (ref "U2") (pin "5") (pinfunction "RXD_5") (pintype "input"))
    )
    (net (code "34") (name "Net-(R11-P$2)") (class "Default")
      (node (ref "$$U$3") (pin "D1") (pinfunction "D1_D1") (pintype "bidirectional"))
      (node (ref "JP3") (pin "3") (pinfunction "3_3") (pintype "passive"))
      (node (ref "R11") (pin "2") (pinfunction "P$2_2") (pintype "passive"))
    )
    (net (code "35") (name "Net-(R12-P$2)") (class "Default")
      (node (ref "$$U$3") (pin "D0") (pinfunction "D0_D0") (pintype "bidirectional"))
      (node (ref "JP3") (pin "2") (pinfunction "2_2") (pintype "passive"))
      (node (ref "R12") (pin "2") (pinfunction "P$2_2") (pintype "passive"))
    )
    (net (code "36") (name "Net-(R14-P$1)") (class "Default")
      (node (ref "R14") (pin "1") (pinfunction "P$1_1") (pintype "passive"))
      (node (ref "U2") (pin "22") (pinfunction "CBUS1_22") (pintype "bidirectional"))
    )
    (net (code "37") (name "Net-(R15-P$1)") (class "Default")
      (node (ref "R15") (pin "1") (pinfunction "P$1_1") (pintype "passive"))
      (node (ref "U2") (pin "23") (pinfunction "CBUS0_23") (pintype "bidirectional"))
    )
    (net (code "38") (name "Net-(R19-P$1)") (class "Default")
      (node (ref "R19") (pin "1") (pinfunction "P$1_1") (pintype "passive"))
      (node (ref "U6") (pin "42") (pinfunction "RSVD_42") (pintype "passive"))
    )
    (net (code "39") (name "Net-(R20-P$1)") (class "Default")
      (node (ref "R20") (pin "1") (pinfunction "P$1_1") (pintype "passive"))
      (node (ref "U6") (pin "41") (pinfunction "RSVD_41") (pintype "passive"))
    )
    (net (code "40") (name "Net-(R21-P$1)") (class "Default")
      (node (ref "R21") (pin "1") (pinfunction "P$1_1") (pintype "passive"))
      (node (ref "U6") (pin "40") (pinfunction "RSVD_40") (pintype "passive"))
    )
    (net (code "41") (name "Net-(R22-P$1)") (class "Default")
      (node (ref "R22") (pin "1") (pinfunction "P$1_1") (pintype "passive"))
      (node (ref "U6") (pin "39") (pinfunction "RSVD_39") (pintype "passive"))
    )
    (net (code "42") (name "Net-(R23-P$1)") (class "Default")
      (node (ref "R23") (pin "1") (pinfunction "P$1_1") (pintype "passive"))
      (node (ref "U2") (pin "1") (pinfunction "TXD_1") (pintype "output"))
    )
    (net (code "43") (name "Net-(R24-P$1)") (class "Default")
      (node (ref "R24") (pin "1") (pinfunction "P$1_1") (pintype "passive"))
      (node (ref "U6") (pin "38") (pinfunction "RSVD_38") (pintype "passive"))
    )
    (net (code "44") (name "Net-(R34-P$2)") (class "Default")
      (node (ref "R34") (pin "2") (pinfunction "P$2_2") (pintype "passive"))
      (node (ref "U6") (pin "10") (pinfunction "EXRES1_10") (pintype "passive"))
    )
    (net (code "45") (name "Net-(R37-P$3-Pad3)") (class "Default")
      (node (ref "R37") (pin "3") (pinfunction "P$3_3") (pintype "passive"))
      (node (ref "R37") (pin "P$2") (pinfunction "P$3_P$2") (pintype "passive"))
      (node (ref "S6") (pin "3") (pinfunction "3_3") (pintype "passive"))
    )
    (net (code "46") (name "Net-(R40-P$2)") (class "Default")
      (node (ref "R40") (pin "2") (pinfunction "P$2_2") (pintype "passive"))
      (node (ref "U6") (pin "23") (pinfunction "RSVD_23") (pintype "passive"))
    )
    (net (code "47") (name "Net-(U5-VOUT)") (class "Default")
      (node (ref "S6") (pin "2") (pinfunction "2_2") (pintype "passive"))
      (node (ref "U5") (pin "2") (pinfunction "VOUT_2") (pintype "passive"))
    )
    (net (code "48") (name "Net-(U6-PMODE0)") (class "Default")
      (node (ref "R16") (pin "2") (pinfunction "2_2") (pintype "passive"))
      (node (ref "U6") (pin "45") (pinfunction "PMODE0_45") (pintype "passive"))
    )
    (net (code "49") (name "Net-(U6-PMODE1)") (class "Default")
      (node (ref "R17") (pin "2") (pinfunction "2_2") (pintype "passive"))
      (node (ref "U6") (pin "44") (pinfunction "PMODE1_44") (pintype "passive"))
    )
    (net (code "50") (name "Net-(U6-PMODE2)") (class "Default")
      (node (ref "R18") (pin "2") (pinfunction "2_2") (pintype "passive"))
      (node (ref "U6") (pin "43") (pinfunction "PMODE2_43") (pintype "passive"))
    )
    (net (code "51") (name "Net-(U6-TOCAP)") (class "Default")
      (node (ref "C30") (pin "P$2") (pinfunction "P$2_P$2") (pintype "passive"))
      (node (ref "U6") (pin "20") (pinfunction "TOCAP_20") (pintype "passive"))
    )
    (net (code "52") (name "PIO0_1{slash}ISP") (class "Default")
      (node (ref "JP2") (pin "14") (pinfunction "14_14") (pintype "passive"))
      (node (ref "R10") (pin "1") (pinfunction "P$1_1") (pintype "passive"))
      (node (ref "R3") (pin "2") (pinfunction "P$2_2") (pintype "passive"))
      (node (ref "S2") (pin "3") (pinfunction "2.1_3") (pintype "passive"))
      (node (ref "S2") (pin "4") (pinfunction "2.2_4") (pintype "passive"))
      (node (ref "U3") (pin "3") (pinfunction "PIO0_1/CLKOUT/CT32B0_MAT2_3") (pintype "bidirectional"))
    )
    (net (code "53") (name "PIO0_2{slash}SSEL0") (class "Default")
      (node (ref "JP2") (pin "9") (pinfunction "9_9") (pintype "passive"))
      (node (ref "R27") (pin "1") (pinfunction "P$1_1") (pintype "passive"))
      (node (ref "U3") (pin "8") (pinfunction "PIO0_2/SSEL0/CT16B0_CAP0_8") (pintype "bidirectional"))
      (node (ref "U6") (pin "32") (pinfunction "SCS_N_32") (pintype "passive"))
    )
    (net (code "54") (name "PIO0_3{slash}W5500_RST") (class "Default")
      (node (ref "JP2") (pin "7") (pinfunction "7_7") (pintype "passive"))
      (node (ref "R25") (pin "1") (pinfunction "P$1_1") (pintype "passive"))
      (node (ref "U3") (pin "9") (pinfunction "PIO0_3_9") (pintype "bidirectional"))
      (node (ref "U6") (pin "37") (pinfunction "RST_N_37") (pintype "passive"))
    )
    (net (code "55") (name "PIO0_4{slash}SCL") (class "Default")
      (node (ref "$$U$3") (pin "SCL") (pinfunction "SCL_SCL") (pintype "bidirectional"))
      (node (ref "C23") (pin "2") (pinfunction "P$2_2") (pintype "passive"))
      (node (ref "JP1") (pin "1") (pinfunction "1_1") (pintype "passive"))
      (node (ref "R36") (pin "1") (pinfunction "P$1_1") (pintype "passive"))
      (node (ref "S5") (pin "3") (pinfunction "2.1_3") (pintype "passive"))
      (node (ref "S5") (pin "4") (pinfunction "2.2_4") (pintype "passive"))
      (node (ref "U3") (pin "10") (pinfunction "PIO0_4/SCL_10") (pintype "bidirectional"))
    )
    (net (code "56") (name "PIO0_5{slash}SDA") (class "Default")
      (node (ref "$$U$3") (pin "SDA") (pinfunction "SDA_SDA") (pintype "bidirectional"))
      (node (ref "C14") (pin "2") (pinfunction "P$2_2") (pintype "passive"))
      (node (ref "JP1") (pin "2") (pinfunction "2_2") (pintype "passive"))
      (node (ref "R28") (pin "1") (pinfunction "P$1_1") (pintype "passive"))
      (node (ref "S4") (pin "3") (pinfunction "2.1_3") (pintype "passive"))
      (node (ref "S4") (pin "4") (pinfunction "2.2_4") (pintype "passive"))
      (node (ref "U3") (pin "11") (pinfunction "PIO0_5/SDA_11") (pintype "bidirectional"))
    )
    (net (code "57") (name "PIO0_6{slash}SCK0") (class "Default")
      (node (ref "$$U$3") (pin "D13") (pinfunction "D13_D13") (pintype "bidirectional"))
      (node (ref "$$U$3") (pin "SCK") (pinfunction "SCK_SCK") (pintype "passive"))
      (node (ref "JP1") (pin "3") (pinfunction "3_3") (pintype "passive"))
      (node (ref "U3") (pin "15") (pinfunction "PIO0_6/R/SCK0_15") (pintype "bidirectional"))
      (node (ref "U4") (pin "2") (pinfunction "SCK_2") (pintype "passive"))
      (node (ref "U6") (pin "33") (pinfunction "SCLK_33") (pintype "passive"))
    )
    (net (code "58") (name "PIO0_7{slash}INT_N") (class "Default")
      (node (ref "JP2") (pin "8") (pinfunction "8_8") (pintype "passive"))
      (node (ref "R26") (pin "1") (pinfunction "P$1_1") (pintype "passive"))
      (node (ref "U3") (pin "16") (pinfunction "PIO0_7/~{CTS}_16") (pintype "bidirectional"))
      (node (ref "U6") (pin "36") (pinfunction "INT_N_36") (pintype "passive"))
    )
    (net (code "59") (name "PIO0_8{slash}MISO0") (class "Default")
      (node (ref "$$U$3") (pin "D12") (pinfunction "D12_D12") (pintype "bidirectional"))
      (node (ref "$$U$3") (pin "MISO") (pinfunction "MISO_MISO") (pintype "passive"))
      (node (ref "JP1") (pin "4") (pinfunction "4_4") (pintype "passive"))
      (node (ref "U3") (pin "17") (pinfunction "PIO0_8/MISO0/CT16B0_MAT0_17") (pintype "bidirectional"))
      (node (ref "U4") (pin "8") (pinfunction "SO_8") (pintype "passive"))
      (node (ref "U6") (pin "34") (pinfunction "MISO_34") (pintype "passive"))
    )
    (net (code "60") (name "PIO0_9{slash}MOSI0") (class "Default")
      (node (ref "$$U$3") (pin "D11") (pinfunction "D11_D11") (pintype "bidirectional"))
      (node (ref "$$U$3") (pin "MOSI") (pinfunction "MOSI_MOSI") (pintype "passive"))
      (node (ref "JP1") (pin "5") (pinfunction "5_5") (pintype "passive"))
      (node (ref "U3") (pin "18") (pinfunction "PIO0_9/MOSI0/CT16B0_MAT1/SWO_18") (pintype "bidirectional"))
      (node (ref "U4") (pin "1") (pinfunction "SI_1") (pintype "passive"))
      (node (ref "U6") (pin "35") (pinfunction "MOSI_35") (pintype "passive"))
    )
    (net (code "61") (name "PIO0_11{slash}AD0") (class "Default")
      (node (ref "JP2") (pin "11") (pinfunction "11_11") (pintype "passive"))
      (node (ref "S6") (pin "1") (pinfunction "1_1") (pintype "passive"))
      (node (ref "U3") (pin "21") (pinfunction "TDI/PIO0_11/AD0/CT32B0_MAT3_21") (pintype "bidirectional"))
    )
    (net (code "62") (name "PIO0_12{slash}AD1") (class "Default")
      (node (ref "$$U$3") (pin "A1") (pinfunction "A1_A1") (pintype "bidirectional"))
      (node (ref "JP2") (pin "12") (pinfunction "12_12") (pintype "passive"))
      (node (ref "U3") (pin "22") (pinfunction "TMS/PIO0_12/AD1/CT32B1_CAP0_22") (pintype "bidirectional"))
    )
    (net (code "63") (name "PIO0_13{slash}AD2") (class "Default")
      (node (ref "$$U$3") (pin "A2") (pinfunction "A2_A2") (pintype "bidirectional"))
      (node (ref "JP2") (pin "13") (pinfunction "13_13") (pintype "passive"))
      (node (ref "U3") (pin "23") (pinfunction "TDO/PIO0_13/AD2/CT32B1_MAT0_23") (pintype "bidirectional"))
    )
    (net (code "64") (name "PIO0_14{slash}AD3") (class "Default")
      (node (ref "$$U$3") (pin "A3") (pinfunction "A3_A3") (pintype "bidirectional"))
      (node (ref "$$U$3") (pin "D4") (pinfunction "D4_D4") (pintype "bidirectional"))
      (node (ref "JP1") (pin "12") (pinfunction "12_12") (pintype "passive"))
      (node (ref "U3") (pin "24") (pinfunction "~{TRST}/PIO0_14/AD3/CT32B1_MAT1_24") (pintype "bidirectional"))
    )
    (net (code "65") (name "PIO0_16{slash}AD5") (class "Default")
      (node (ref "$$U$3") (pin "A4") (pinfunction "A4_A4") (pintype "bidirectional"))
      (node (ref "$$U$3") (pin "D5") (pinfunction "D5_D5") (pintype "bidirectional"))
      (node (ref "JP1") (pin "11") (pinfunction "11_11") (pintype "passive"))
      (node (ref "U3") (pin "26") (pinfunction "PIO0_16/AD5/CT32B1_MAT3/WAKEUP_26") (pintype "bidirectional"))
    )
    (net (code "66") (name "PIO0_17") (class "Default")
      (node (ref "$$U$3") (pin "D3") (pinfunction "D3_D3") (pintype "bidirectional"))
      (node (ref "JP1") (pin "13") (pinfunction "13_13") (pintype "passive"))
      (node (ref "U3") (pin "30") (pinfunction "PIO0_17/~{RTS}/CT32B0_CAP0_30") (pintype "bidirectional"))
    )
    (net (code "67") (name "PIO0_18{slash}RXD") (class "Default")
      (node (ref "JP1") (pin "16") (pinfunction "16_16") (pintype "passive"))
      (node (ref "R12") (pin "1") (pinfunction "P$1_1") (pintype "passive"))
      (node (ref "R23") (pin "2") (pinfunction "P$2_2") (pintype "passive"))
      (node (ref "U3") (pin "31") (pinfunction "PIO0_18/RXD/CT32B0_MAT0_31") (pintype "bidirectional"))
    )
    (net (code "68") (name "PIO0_19{slash}TXD") (class "Default")
      (node (ref "JP1") (pin "15") (pinfunction "15_15") (pintype "passive"))
      (node (ref "R11") (pin "1") (pinfunction "P$1_1") (pintype "passive"))
      (node (ref "R9") (pin "2") (pinfunction "P$2_2") (pintype "passive"))
      (node (ref "U3") (pin "32") (pinfunction "PIO0_19/TXD/CT32B0_MAT1_32") (pintype "bidirectional"))
    )
    (net (code "69") (name "PIO0_20") (class "Default")
      (node (ref "$$U$3") (pin "D7") (pinfunction "D7_D7") (pintype "bidirectional"))
      (node (ref "JP1") (pin "9") (pinfunction "9_9") (pintype "passive"))
      (node (ref "U3") (pin "7") (pinfunction "PIO0_20/CT16B1_CAP0_7") (pintype "bidirectional"))
    )
    (net (code "70") (name "PIO0_22{slash}AD6") (class "Default")
      (node (ref "$$U$3") (pin "A0") (pinfunction "A0_A0") (pintype "bidirectional"))
      (node (ref "JP2") (pin "10") (pinfunction "10_10") (pintype "passive"))
      (node (ref "U3") (pin "20") (pinfunction "PIO0_22/AD6/CT16B1_MAT1/MISO1_20") (pintype "bidirectional"))
    )
    (net (code "71") (name "PIO0_23{slash}AD7") (class "Default")
      (node (ref "$$U$3") (pin "A5") (pinfunction "A5_A5") (pintype "bidirectional"))
      (node (ref "$$U$3") (pin "D6") (pinfunction "D6_D6") (pintype "bidirectional"))
      (node (ref "JP1") (pin "10") (pinfunction "10_10") (pintype "passive"))
      (node (ref "U3") (pin "27") (pinfunction "PIO0_23/AD7_27") (pintype "bidirectional"))
    )
    (net (code "72") (name "PIO1_15") (class "Default")
      (node (ref "$$U$3") (pin "D2") (pinfunction "D2_D2") (pintype "bidirectional"))
      (node (ref "JP1") (pin "14") (pinfunction "14_14") (pintype "passive"))
      (node (ref "U3") (pin "28") (pinfunction "PIO1_15/~{DCD}/CT16B0_MAT2/SCK1_28") (pintype "bidirectional"))
    )
    (net (code "73") (name "PIO1_19{slash}SSEL1") (class "Default")
      (node (ref "JP1") (pin "17") (pinfunction "17_17") (pintype "passive"))
      (node (ref "U3") (pin "1") (pinfunction "PIO1_19/~{DTR}/SSEL1_1") (pintype "bidirectional"))
      (node (ref "U4") (pin "4") (pinfunction "~{CS}_4") (pintype "passive"))
    )
    (net (code "74") (name "PIO1_21{slash}LEDR") (class "Default")
      (node (ref "$$U$3") (pin "D8") (pinfunction "D8_D8") (pintype "bidirectional"))
      (node (ref "JP1") (pin "8") (pinfunction "8_8") (pintype "passive"))
      (node (ref "R5") (pin "1") (pinfunction "P$1_1") (pintype "passive"))
      (node (ref "U3") (pin "12") (pinfunction "PIO0_21/CT16B1_MAT0/MOSI1_12") (pintype "bidirectional"))
    )
    (net (code "75") (name "PIO1_23{slash}LEDG") (class "Default")
      (node (ref "$$U$3") (pin "D9") (pinfunction "D9_D9") (pintype "bidirectional"))
      (node (ref "JP1") (pin "7") (pinfunction "7_7") (pintype "passive"))
      (node (ref "R6") (pin "1") (pinfunction "P$1_1") (pintype "passive"))
      (node (ref "U3") (pin "13") (pinfunction "PIO1_23/CT16B1_MAT1/SSEL1_13") (pintype "bidirectional"))
    )
    (net (code "76") (name "PIO1_24{slash}LEDB") (class "Default")
      (node (ref "$$U$3") (pin "D10") (pinfunction "D10_D10") (pintype "bidirectional"))
      (node (ref "JP1") (pin "6") (pinfunction "6_6") (pintype "passive"))
      (node (ref "R4") (pin "1") (pinfunction "P$1_1") (pintype "passive"))
      (node (ref "U3") (pin "14") (pinfunction "PIO1_24/CT32B0_MAT0_14") (pintype "bidirectional"))
    )
    (net (code "77") (name "RXN") (class "Default")
      (node (ref "C25") (pin "2") (pinfunction "P$2_2") (pintype "passive"))
      (node (ref "R33") (pin "2") (pinfunction "P$2_2") (pintype "passive"))
      (node (ref "U6") (pin "5") (pinfunction "RXN_5") (pintype "passive"))
    )
    (net (code "78") (name "RXP") (class "Default")
      (node (ref "C18") (pin "2") (pinfunction "P$2_2") (pintype "passive"))
      (node (ref "R32") (pin "2") (pinfunction "P$2_2") (pintype "passive"))
      (node (ref "U6") (pin "6") (pinfunction "RXP_6") (pintype "passive"))
    )
    (net (code "79") (name "SWCLK{slash}PIO0_10") (class "Default")
      (node (ref "J2") (pin "4") (pinfunction "4_4") (pintype "passive"))
      (node (ref "JP2") (pin "16") (pinfunction "16_16") (pintype "passive"))
      (node (ref "U3") (pin "19") (pinfunction "SWCLK/PIO0_10/SCK0/CT16B0_MAT2_19") (pintype "bidirectional"))
    )
    (net (code "80") (name "SWDIO{slash}PIO0_15") (class "Default")
      (node (ref "J2") (pin "2") (pinfunction "2_2") (pintype "passive"))
      (node (ref "JP2") (pin "15") (pinfunction "15_15") (pintype "passive"))
      (node (ref "U3") (pin "25") (pinfunction "SWDIO/PIO0_15/AD4/CT32B1_MAT2_25") (pintype "bidirectional"))
    )
    (net (code "81") (name "TXN") (class "Default")
      (node (ref "P1") (pin "3") (pinfunction "TD-_3") (pintype "passive"))
      (node (ref "R31") (pin "1") (pinfunction "P$1_1") (pintype "passive"))
      (node (ref "U6") (pin "1") (pinfunction "TXN_1") (pintype "passive"))
    )
    (net (code "82") (name "TXP") (class "Default")
      (node (ref "P1") (pin "1") (pinfunction "TD+_1") (pintype "passive"))
      (node (ref "R29") (pin "1") (pinfunction "P$1_1") (pintype "passive"))
      (node (ref "U6") (pin "2") (pinfunction "TXP_2") (pintype "passive"))
    )
    (net (code "83") (name "VCCIO") (class "Default")
      (node (ref "C2") (pin "2") (pinfunction "P$2_2") (pintype "passive"))
      (node (ref "LED3") (pin "1") (pinfunction "P$1_1") (pintype "bidirectional"))
      (node (ref "LED4") (pin "1") (pinfunction "P$1_1") (pintype "bidirectional"))
      (node (ref "U2") (pin "17") (pinfunction "3V3OUT_17") (pintype "output"))
      (node (ref "U2") (pin "19") (pinfunction "~{RESET}_19") (pintype "input"))
      (node (ref "U2") (pin "4") (pinfunction "VCCIO_4") (pintype "power_in"))
    )
    (net (code "84") (name "VCC{slash}2") (class "Default")
      (node (ref "C12") (pin "1") (pinfunction "1_1") (pintype "passive"))
      (node (ref "C4") (pin "2") (pinfunction "P$2_2") (pintype "passive"))
      (node (ref "D2") (pin "2") (pinfunction "2_2") (pintype "bidirectional"))
      (node (ref "L1") (pin "2") (pinfunction "2_2") (pintype "passive"))
      (node (ref "TP1") (pin "TP") (pinfunction "TP_TP") (pintype "input"))
      (node (ref "U2") (pin "20") (pinfunction "VCC_20") (pintype "power_in"))
    )
    (net (code "85") (name "VIN") (class "Default")
      (node (ref "$$U$3") (pin "VIN") (pinfunction "VIN_VIN") (pintype "power_in"))
    )
    (net (code "86") (name "unconnected-($$U$3-PadRESERVED)") (class "Default")
      (node (ref "$$U$3") (pin "RESERVED") (pinfunction "RESERVED_RESERVED") (pintype "no_connect"))
    )
    (net (code "87") (name "unconnected-(J2-Pad6)") (class "Default")
      (node (ref "J2") (pin "6") (pinfunction "6_6") (pintype "passive"))
    )
    (net (code "88") (name "unconnected-(J2-Pad8)") (class "Default")
      (node (ref "J2") (pin "8") (pinfunction "8_8") (pintype "passive"))
    )
    (net (code "89") (name "unconnected-(P1-NC-Pad7)") (class "Default")
      (node (ref "P1") (pin "7") (pinfunction "NC_7") (pintype "passive"))
    )
    (net (code "90") (name "unconnected-(S1-Pad3)") (class "Default")
      (node (ref "S1") (pin "3") (pinfunction "3_3") (pintype "passive"))
    )
    (net (code "91") (name "unconnected-(U2-CBUS2-Pad13)") (class "Default")
      (node (ref "U2") (pin "13") (pinfunction "CBUS2_13") (pintype "bidirectional"))
    )
    (net (code "92") (name "unconnected-(U2-CBUS3-Pad14)") (class "Default")
      (node (ref "U2") (pin "14") (pinfunction "CBUS3_14") (pintype "bidirectional"))
    )
    (net (code "93") (name "unconnected-(U2-CBUS4-Pad12)") (class "Default")
      (node (ref "U2") (pin "12") (pinfunction "CBUS4_12") (pintype "bidirectional"))
    )
    (net (code "94") (name "unconnected-(U2-OSCI-Pad27)") (class "Default")
      (node (ref "U2") (pin "27") (pinfunction "OSCI_27") (pintype "input"))
    )
    (net (code "95") (name "unconnected-(U2-OSCO-Pad28)") (class "Default")
      (node (ref "U2") (pin "28") (pinfunction "OSCO_28") (pintype "output"))
    )
    (net (code "96") (name "unconnected-(U2-~{CTS}-Pad11)") (class "Default")
      (node (ref "U2") (pin "11") (pinfunction "~{CTS}_11") (pintype "input"))
    )
    (net (code "97") (name "unconnected-(U2-~{DCD}-Pad10)") (class "Default")
      (node (ref "U2") (pin "10") (pinfunction "~{DCD}_10") (pintype "input"))
    )
    (net (code "98") (name "unconnected-(U2-~{DSR}-Pad9)") (class "Default")
      (node (ref "U2") (pin "9") (pinfunction "~{DSR}_9") (pintype "input"))
    )
    (net (code "99") (name "unconnected-(U2-~{DTR}-Pad2)") (class "Default")
      (node (ref "U2") (pin "2") (pinfunction "~{DTR}_2") (pintype "output"))
    )
    (net (code "100") (name "unconnected-(U2-~{RI}-Pad6)") (class "Default")
      (node (ref "U2") (pin "6") (pinfunction "~{RI}_6") (pintype "input"))
    )
    (net (code "101") (name "unconnected-(U2-~{RTS}-Pad3)") (class "Default")
      (node (ref "U2") (pin "3") (pinfunction "~{RTS}_3") (pintype "output"))
    )
    (net (code "102") (name "unconnected-(U6-DNC-Pad7)") (class "Default")
      (node (ref "U6") (pin "7") (pinfunction "DNC_7") (pintype "passive"))
    )
    (net (code "103") (name "unconnected-(U6-DUPLED-Pad26)") (class "Default")
      (node (ref "U6") (pin "26") (pinfunction "DUPLED_26") (pintype "passive"))
    )
    (net (code "104") (name "unconnected-(U6-NC-Pad12)") (class "Default")
      (node (ref "U6") (pin "12") (pinfunction "NC_12") (pintype "passive"))
    )
    (net (code "105") (name "unconnected-(U6-NC-Pad13)") (class "Default")
      (node (ref "U6") (pin "13") (pinfunction "NC_13") (pintype "passive"))
    )
    (net (code "106") (name "unconnected-(U6-NC-Pad46)") (class "Default")
      (node (ref "U6") (pin "46") (pinfunction "NC_46") (pintype "passive"))
    )
    (net (code "107") (name "unconnected-(U6-NC-Pad47)") (class "Default")
      (node (ref "U6") (pin "47") (pinfunction "NC_47") (pintype "passive"))
    )
    (net (code "108") (name "unconnected-(U6-SPDLED-Pad24)") (class "Default")
      (node (ref "U6") (pin "24") (pinfunction "SPDLED_24") (pintype "passive"))
    )
    (net (code "109") (name "unconnected-(U6-VBG-Pad18)") (class "Default")
      (node (ref "U6") (pin "18") (pinfunction "VBG_18") (pintype "passive"))
    )
    (net (code "110") (name "unconnected-(X1-Pad4)") (class "Default")
      (node (ref "X1") (pin "4") (pinfunction "4_4") (pintype "passive"))
    )
    (net (code "111") (name "unconnected-(Y1-Pad2)") (class "Default")
      (node (ref "Y1") (pin "2") (pinfunction "2_2") (pintype "passive"))
    )
    (net (code "112") (name "unconnected-(Y1-Pad4)") (class "Default")
      (node (ref "Y1") (pin "4") (pinfunction "4_4") (pintype "passive"))
    )
    (net (code "113") (name "unconnected-(Y2-Pad2)") (class "Default")
      (node (ref "Y2") (pin "2") (pinfunction "2_2") (pintype "passive"))
    )
    (net (code "114") (name "unconnected-(Y2-Pad4)") (class "Default")
      (node (ref "Y2") (pin "4") (pinfunction "4_4") (pintype "passive"))
    )
    (net (code "115") (name "~{RESET}{slash}PIO0_0") (class "Default")
      (node (ref "$$U$3") (pin "RESET") (pinfunction "/RESET_RESET") (pintype "bidirectional"))
      (node (ref "$$U$3") (pin "RESET_ICSP") (pinfunction "RST_RESET_ICSP") (pintype "passive"))
      (node (ref "C10") (pin "2") (pinfunction "P$2_2") (pintype "passive"))
      (node (ref "J2") (pin "10") (pinfunction "10_10") (pintype "passive"))
      (node (ref "JP2") (pin "17") (pinfunction "17_17") (pintype "passive"))
      (node (ref "R13") (pin "1") (pinfunction "P$1_1") (pintype "passive"))
      (node (ref "S3") (pin "3") (pinfunction "2.1_3") (pintype "passive"))
      (node (ref "S3") (pin "4") (pinfunction "2.2_4") (pintype "passive"))
      (node (ref "U3") (pin "2") (pinfunction "~{RESET}/PIO0_0_2") (pintype "bidirectional"))
      (node (ref "U4") (pin "3") (pinfunction "~{RESET}_3") (pintype "passive"))
    )
  )
)
